# AntennaSchematic.net
KiCad netlist of a schematic drawn in Altium Designer
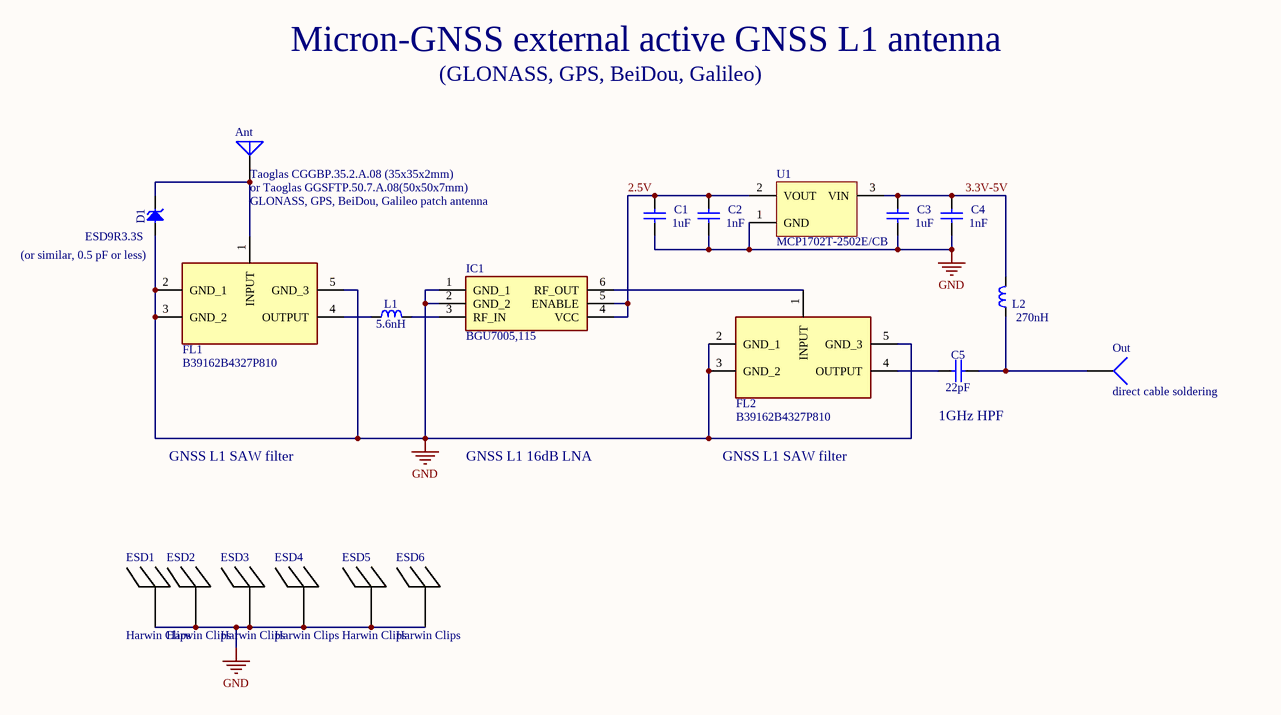
[diagram p0: AntennaSchematic.SchDoc]

(export (version "E")
  (design (tool "Eeschema 10.0.6"))
  (components
    (comp (ref "Ant")
      (value "Taoglas CGGBP.35.2.A.08 (35x35x2mm)")
      (footprint "PIN1")
      (description "Generic Antenna")
      (fields (field (name "PUBLISHER") "Altium Limited"))
      (libsource (lib "Miscellaneous Devices") (part "Antenna"))
    )
    (comp (ref "C1")
      (value "1uF")
      (footprint "CAPC1005X55N")
      (description "Non-polarised capacitor")
      (fields
        (field (name "PART NUMBER") "CC0402_10NF_50V_10%_X7R")
        (field (name "VOLTAGE") "50V")
        (field (name "AUTHOR") "CERN DEM MR")
      )
      (libsource (lib "Capacitors") (part "Capacitor - non polarized"))
    )
    (comp (ref "C2")
      (value "1nF")
      (footprint "CAPC1005X55N")
      (description "Non-polarised capacitor")
      (fields
        (field (name "PART NUMBER") "CC0402_10NF_50V_10%_X7R")
        (field (name "VOLTAGE") "50V")
        (field (name "AUTHOR") "CERN DEM MR")
      )
      (libsource (lib "Capacitors") (part "Capacitor - non polarized"))
    )
    (comp (ref "C3")
      (value "1uF")
      (footprint "CAPC1005X55N")
      (description "Non-polarised capacitor")
      (fields
        (field (name "PART NUMBER") "CC0402_10NF_50V_10%_X7R")
        (field (name "VOLTAGE") "50V")
        (field (name "AUTHOR") "CERN DEM MR")
      )
      (libsource (lib "Capacitors") (part "Capacitor - non polarized"))
    )
    (comp (ref "C4")
      (value "1nF")
      (footprint "CAPC1005X55N")
      (description "Non-polarised capacitor")
      (fields
        (field (name "PART NUMBER") "CC0402_10NF_50V_10%_X7R")
        (field (name "VOLTAGE") "50V")
        (field (name "AUTHOR") "CERN DEM MR")
      )
      (libsource (lib "Capacitors") (part "Capacitor - non polarized"))
    )
    (comp (ref "C5")
      (value "22pF")
      (footprint "CAPC1005X55N")
      (description "Non-polarised capacitor")
      (fields
        (field (name "PART NUMBER") "CC0402_10NF_50V_10%_X7R")
        (field (name "VOLTAGE") "50V")
        (field (name "AUTHOR") "CERN DEM MR")
      )
      (libsource (lib "Capacitors") (part "Capacitor - non polarized"))
    )
    (comp (ref "D1")
      (value "ESD9R3.3S")
      (footprint "SOD2512X110N")
      (description "Transient Voltage Suppressor Diode (Uni-Directional)")
      (fields
        (field (name "PART NUMBER") "PESD5V0S1UA")
        (field (name "VOLTAGE") "5V")
        (field (name "AUTHOR") "CERN DEM JLC")
      )
      (libsource (lib "ICs And Semiconductors") (part "Diode TVS Uni-Directional"))
    )
    (comp (ref "ESD1")
      (value "Harwin Clips")
      (footprint "HARWIN - S0981-46R - CLIP")
      (libsource (lib "My SCH library") (part "Harwin Clips"))
    )
    (comp (ref "ESD2")
      (value "Harwin Clips")
      (footprint "HARWIN - S0981-46R - CLIP")
      (libsource (lib "My SCH library") (part "Harwin Clips"))
    )
    (comp (ref "ESD3")
      (value "Harwin Clips")
      (footprint "HARWIN - S0981-46R - CLIP")
      (libsource (lib "My SCH library") (part "Harwin Clips"))
    )
    (comp (ref "ESD4")
      (value "Harwin Clips")
      (footprint "HARWIN - S0981-46R - CLIP")
      (libsource (lib "My SCH library") (part "Harwin Clips"))
    )
    (comp (ref "ESD5")
      (value "Harwin Clips")
      (footprint "HARWIN - S0991-46R - CLIP")
      (libsource (lib "My SCH library") (part "Harwin Clips"))
    )
    (comp (ref "ESD6")
      (value "Harwin Clips")
      (footprint "HARWIN - S0991-46R - CLIP")
      (libsource (lib "My SCH library") (part "Harwin Clips"))
    )
    (comp (ref "FL1")
      (value "B39162B4327P810")
      (footprint "SamacSys:B39921B4344P810")
      (description "Filter")
      (libsource (lib "*") (part "B39162B4327P810"))
    )
    (comp (ref "FL2")
      (value "B39162B4327P810")
      (footprint "SamacSys:B39921B4344P810")
      (description "Filter")
      (libsource (lib "*") (part "B39162B4327P810"))
    )
    (comp (ref "IC1")
      (value "BGU7005,115")
      (footprint "SamacSys:SL3S1013FTB0115")
      (description "Integrated Circuit")
      (fields (field (name "MOUSER PART NUMBER") "771-BGU7005115"))
      (libsource (lib "*") (part "BGU7005,115"))
    )
    (comp (ref "L1")
      (value "5.6nH")
      (footprint "INDC1005X55N")
      (description "Inductor")
      (fields
        (field (name "PART NUMBER") "IND0402_MURATA_BLM15HD601SN1")
        (field (name "POWER") "300mA")
        (field (name "AUTHOR") "CERN DEM JLC")
      )
      (libsource (lib "Inductors & Transformers") (part "Inductor"))
    )
    (comp (ref "L2")
      (value "270nH")
      (footprint "INDC1005X55N")
      (description "Inductor")
      (fields
        (field (name "PART NUMBER") "IND0402_MURATA_BLM15HD601SN1")
        (field (name "POWER") "300mA")
        (field (name "AUTHOR") "CERN DEM JLC")
      )
      (libsource (lib "") (part "Inductor_1"))
    )
    (comp (ref "Out")
      (value "direct cable soldering")
      (footprint "PIN1")
      (fields (field (name "PUBLISHER") "Altium Limited"))
      (libsource (lib "Miscellaneous Connectors") (part "Socket"))
    )
    (comp (ref "U1")
      (value "MCP1702T-2502E/CB")
      (footprint "SOT-23A-CB3_N")
      (description "250 mA Low Quiescent Current LDO Regulator, 3-Pin SOT-23A, Extended Temperature, Tape and Reel")
      (fields (field (name "PUBLISHER") "Altium Limited"))
      (libsource (lib "Microchip Power Mgt Line Regulator") (part "MCP1702T-2502E/CB"))
    )
  )
  (nets
    (net (code "1") (name "/2.5V") (class "Default")
      (node (ref "C1") (pin "2") (pinfunction "2_2") (pintype "passive"))
      (node (ref "C2") (pin "2") (pinfunction "2_2") (pintype "passive"))
      (node (ref "IC1") (pin "4") (pinfunction "VCC_4") (pintype "passive"))
      (node (ref "IC1") (pin "5") (pinfunction "ENABLE_5") (pintype "passive"))
      (node (ref "U1") (pin "2") (pinfunction "VOUT_2") (pintype "power_in"))
    )
    (net (code "2") (name "/3.3V-5V") (class "Default")
      (node (ref "C3") (pin "2") (pinfunction "2_2") (pintype "passive"))
      (node (ref "C4") (pin "2") (pinfunction "2_2") (pintype "passive"))
      (node (ref "L2") (pin "2") (pinfunction "2_2") (pintype "passive"))
      (node (ref "U1") (pin "3") (pinfunction "VIN_3") (pintype "power_in"))
    )
    (net (code "3") (name "GND") (class "Default")
      (node (ref "C1") (pin "1") (pinfunction "1_1") (pintype "passive"))
      (node (ref "C2") (pin "1") (pinfunction "1_1") (pintype "passive"))
      (node (ref "C3") (pin "1") (pinfunction "1_1") (pintype "passive"))
      (node (ref "C4") (pin "1") (pinfunction "1_1") (pintype "passive"))
      (node (ref "D1") (pin "2") (pinfunction "A_2") (pintype "passive"))
      (node (ref "ESD1") (pin "1") (pinfunction "1_1") (pintype "passive"))
      (node (ref "ESD2") (pin "1") (pinfunction "1_1") (pintype "passive"))
      (node (ref "ESD3") (pin "1") (pinfunction "1_1") (pintype "passive"))
      (node (ref "ESD4") (pin "1") (pinfunction "1_1") (pintype "passive"))
      (node (ref "ESD5") (pin "1") (pinfunction "1_1") (pintype "passive"))
      (node (ref "ESD6") (pin "1") (pinfunction "1_1") (pintype "passive"))
      (node (ref "FL1") (pin "2") (pinfunction "GND_1_2") (pintype "passive"))
      (node (ref "FL1") (pin "3") (pinfunction "GND_2_3") (pintype "passive"))
      (node (ref "FL1") (pin "5") (pinfunction "GND_3_5") (pintype "passive"))
      (node (ref "FL2") (pin "2") (pinfunction "GND_1_2") (pintype "passive"))
      (node (ref "FL2") (pin "3") (pinfunction "GND_2_3") (pintype "passive"))
      (node (ref "FL2") (pin "5") (pinfunction "GND_3_5") (pintype "passive"))
      (node (ref "IC1") (pin "1") (pinfunction "GND_1_1") (pintype "passive"))
      (node (ref "IC1") (pin "2") (pinfunction "GND_2_2") (pintype "passive"))
      (node (ref "U1") (pin "1") (pinfunction "GND_1") (pintype "power_in"))
    )
    (net (code "4") (name "Net-(Ant-A)") (class "Default")
      (node (ref "Ant") (pin "1") (pinfunction "A_1") (pintype "passive"))
      (node (ref "D1") (pin "1") (pinfunction "C_1") (pintype "passive"))
      (node (ref "FL1") (pin "1") (pinfunction "INPUT_1") (pintype "passive"))
    )
    (net (code "5") (name "Net-(C5-Pad2)") (class "Default")
      (node (ref "C5") (pin "2") (pinfunction "2_2") (pintype "passive"))
      (node (ref "L2") (pin "1") (pinfunction "1_1") (pintype "passive"))
      (node (ref "Out") (pin "1") (pinfunction "1_1") (pintype "passive"))
    )
    (net (code "6") (name "Net-(FL1-OUTPUT)") (class "Default")
      (node (ref "FL1") (pin "4") (pinfunction "OUTPUT_4") (pintype "passive"))
      (node (ref "L1") (pin "1") (pinfunction "1_1") (pintype "passive"))
    )
    (net (code "7") (name "Net-(FL2-INPUT)") (class "Default")
      (node (ref "FL2") (pin "1") (pinfunction "INPUT_1") (pintype "passive"))
      (node (ref "IC1") (pin "6") (pinfunction "RF_OUT_6") (pintype "passive"))
    )
    (net (code "8") (name "Net-(FL2-OUTPUT)") (class "Default")
      (node (ref "C5") (pin "1") (pinfunction "1_1") (pintype "passive"))
      (node (ref "FL2") (pin "4") (pinfunction "OUTPUT_4") (pintype "passive"))
    )
    (net (code "9") (name "Net-(IC1-RF_IN)") (class "Default")
      (node (ref "IC1") (pin "3") (pinfunction "RF_IN_3") (pintype "passive"))
      (node (ref "L1") (pin "2") (pinfunction "2_2") (pintype "passive"))
    )
  )
)
